# Can.net
KiCad netlist of a schematic drawn in Altium Designer
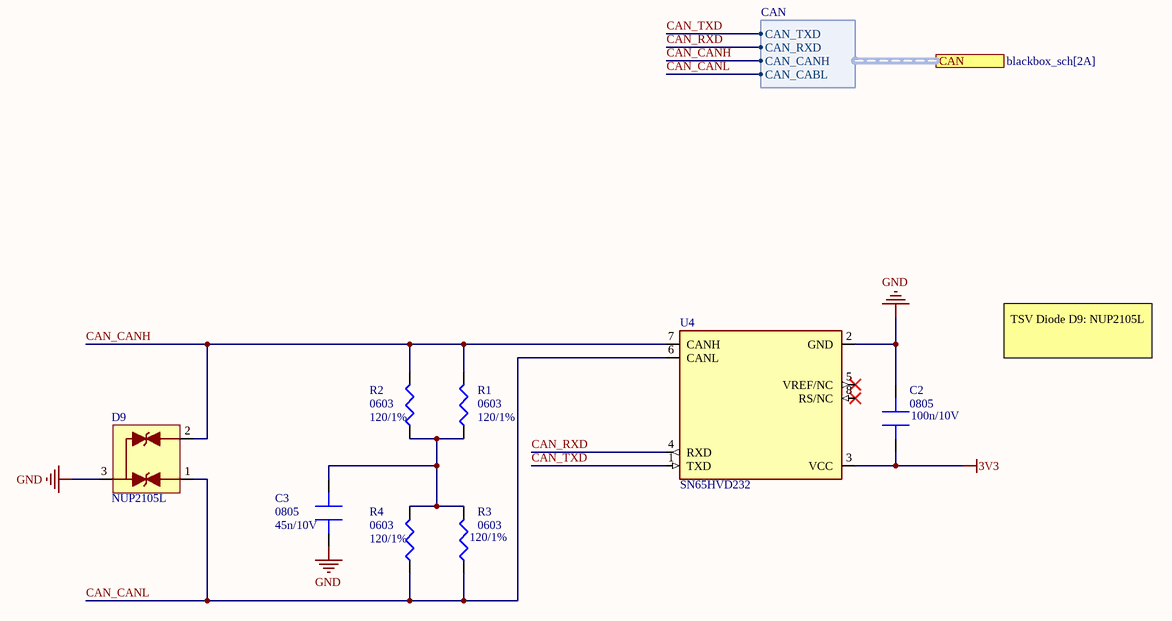
[diagram p0: Can.SchDoc]

(export (version "E")
  (design (tool "Eeschema 10.0.6"))
  (components
    (comp (ref "C2")
      (value "100n/10V")
      (footprint "CAPC2012X09L [0805]")
      (description "Standard capacitor")
      (fields (field (name "PACKAGE") "0805") (field (name "Comment") "C"))
      (libsource (lib "SR_Library") (part "C"))
    )
    (comp (ref "C3")
      (value "45n/10V")
      (footprint "CAPC2012X09L [0805]")
      (description "Standard capacitor")
      (fields (field (name "PACKAGE") "0805") (field (name "Comment") "C"))
      (libsource (lib "SR_Library") (part "C"))
    )
    (comp (ref "D9")
      (value "NUP2105L")
      (footprint "SOT95P237X111-3N [SOT23]")
      (description "ESD protection diode - dual line CAN bus protector")
      (fields (field (name "PN") "NUP2105L"))
      (libsource (lib "_Std_Diodes") (part "NUP2105L"))
    )
    (comp (ref "R1")
      (value "120/1%")
      (footprint "RESC1608X05L [0603]")
      (description "Standard resistor")
      (fields (field (name "PACKAGE") "0603") (field (name "Comment") "R"))
      (libsource (lib "SR_Library") (part "R"))
    )
    (comp (ref "R2")
      (value "120/1%")
      (footprint "RESC1608X05L [0603]")
      (description "Standard resistor")
      (fields (field (name "PACKAGE") "0603") (field (name "Comment") "R"))
      (libsource (lib "_Std_Resistors") (part "R"))
    )
    (comp (ref "R3")
      (value "120/1%")
      (footprint "RESC1608X05L [0603]")
      (description "Standard resistor")
      (fields (field (name "PACKAGE") "0603") (field (name "Comment") "R"))
      (libsource (lib "SR_Library") (part "R"))
    )
    (comp (ref "R4")
      (value "120/1%")
      (footprint "RESC1608X05L [0603]")
      (description "Standard resistor")
      (fields (field (name "PACKAGE") "0603") (field (name "Comment") "R"))
      (libsource (lib "SR_Library") (part "R"))
    )
    (comp (ref "U4")
      (value "SN65HVD23x")
      (footprint "SOIC127P600X175-8N")
      (description "CAN bus transceiver, 3V3")
      (fields (field (name "PN") "SN65HVD232"))
      (libsource (lib "_IC_Interface") (part "SN65HVD23x"))
    )
  )
  (nets
    (net (code "2") (name "/CAN_CANH") (class "Default")
      (node (ref "D9") (pin "2") (pinfunction "2_2") (pintype "passive"))
      (node (ref "R1") (pin "2") (pinfunction "2_2") (pintype "passive"))
      (node (ref "R2") (pin "1") (pinfunction "1_1") (pintype "passive"))
      (node (ref "U4") (pin "7") (pinfunction "CANH_7") (pintype "bidirectional"))
    )
    (net (code "3") (name "/CAN_CANL") (class "Default")
      (node (ref "D9") (pin "1") (pinfunction "1_1") (pintype "passive"))
      (node (ref "R3") (pin "1") (pinfunction "1_1") (pintype "passive"))
      (node (ref "R4") (pin "1") (pinfunction "1_1") (pintype "passive"))
      (node (ref "U4") (pin "6") (pinfunction "CANL_6") (pintype "bidirectional"))
    )
    (net (code "4") (name "/CAN_RXD") (class "Default")
      (node (ref "U4") (pin "4") (pinfunction "RXD_4") (pintype "output"))
    )
    (net (code "5") (name "/CAN_TXD") (class "Default")
      (node (ref "U4") (pin "1") (pinfunction "TXD_1") (pintype "input"))
    )
    (net (code "7") (name "3V3") (class "Default")
      (node (ref "C2") (pin "1") (pinfunction "1_1") (pintype "passive"))
      (node (ref "U4") (pin "3") (pinfunction "VCC_3") (pintype "power_in"))
    )
    (net (code "8") (name "GND") (class "Default")
      (node (ref "C2") (pin "2") (pinfunction "2_2") (pintype "passive"))
      (node (ref "C3") (pin "1") (pinfunction "1_1") (pintype "passive"))
      (node (ref "D9") (pin "3") (pinfunction "3_3") (pintype "passive"))
      (node (ref "U4") (pin "2") (pinfunction "GND_2") (pintype "power_in"))
    )
    (net (code "9") (name "Net-(C3-Pad2)") (class "Default")
      (node (ref "C3") (pin "2") (pinfunction "2_2") (pintype "passive"))
      (node (ref "R1") (pin "1") (pinfunction "1_1") (pintype "passive"))
      (node (ref "R2") (pin "2") (pinfunction "2_2") (pintype "passive"))
      (node (ref "R3") (pin "2") (pinfunction "2_2") (pintype "passive"))
      (node (ref "R4") (pin "2") (pinfunction "2_2") (pintype "passive"))
    )
    (net (code "10") (name "unconnected-(U4-RS{slash}NC-Pad8)") (class "Default")
      (node (ref "U4") (pin "8") (pinfunction "RS/NC_8") (pintype "input+no_connect"))
    )
    (net (code "11") (name "unconnected-(U4-VREF{slash}NC-Pad5)") (class "Default")
      (node (ref "U4") (pin "5") (pinfunction "VREF/NC_5") (pintype "output+no_connect"))
    )
  )
)
